# rs485.net
KiCad netlist of a schematic drawn in Altium Designer
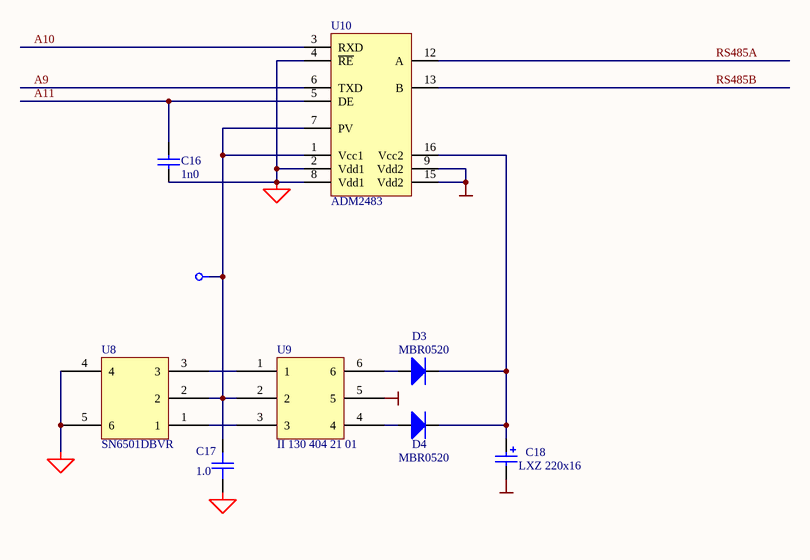
[diagram p0: rs485.SchDoc]

(export (version "E")
  (design (tool "Eeschema 10.0.6"))
  (components
    (comp (ref "C16")
      (value "1n0")
      (footprint "_1206")
      (description "Capacitor (Semiconductor SIM Model)")
      (fields (field (name "MANUFACTURER") "Generic Components") (field (name "PUBLISHER") "Altium Limited"))
      (libsource (lib "Miscellaneous Devices") (part "Cap Semi"))
    )
    (comp (ref "C17") (value "1.0") (footprint "_1206") (libsource (lib "C") (part "C_SM_1206")))
    (comp (ref "C18")
      (value "LXZ 220x16")
      (footprint "el3")
      (description "Polarized Capacitor (Radial)")
      (fields (field (name "MANUFACTURER") "Generic Components") (field (name "PUBLISHER") "Altium Limited"))
      (libsource (lib "PAL") (part "Cap Pol1"))
    )
    (comp (ref "D3")
      (value "MBR0520")
      (footprint "_1206d")
      (description "Default Diode")
      (fields (field (name "MANUFACTURER") "Generic Components") (field (name "PUBLISHER") "Altium Limited"))
      (libsource (lib "PAL") (part "Diode"))
    )
    (comp (ref "D4")
      (value "MBR0520")
      (footprint "_1206d")
      (description "Default Diode")
      (fields (field (name "MANUFACTURER") "Generic Components") (field (name "PUBLISHER") "Altium Limited"))
      (libsource (lib "PAL") (part "Diode"))
    )
    (comp (ref "U8") (value "SN6501DBVR") (footprint "SO-G5/P.95") (libsource (lib "CHIP") (part "PIN6")))
    (comp (ref "U9")
      (value "II 130 404 21 01")
      (footprint "II1304042101")
      (libsource (lib "") (part "PIN6_1"))
    )
    (comp (ref "U10") (value "ADM2483") (footprint "SO-G16/D10.4") (libsource (lib "PAL") (part "ADM2483")))
  )
  (nets
    (net (code "1") (name "+5v") (class "Default")
      (node (ref "C17") (pin "2") (pinfunction "2_2") (pintype "passive"))
      (node (ref "U10") (pin "1") (pinfunction "Vcc1_1") (pintype "passive"))
      (node (ref "U10") (pin "7") (pinfunction "PV_7") (pintype "passive"))
      (node (ref "U8") (pin "2") (pinfunction "2_2") (pintype "passive"))
      (node (ref "U9") (pin "2") (pinfunction "2_2") (pintype "passive"))
    )
    (net (code "2") (name "/A9") (class "Default")
      (node (ref "U10") (pin "6") (pinfunction "TXD_6") (pintype "passive"))
    )
    (net (code "3") (name "/A10") (class "Default")
      (node (ref "U10") (pin "3") (pinfunction "RXD_3") (pintype "passive"))
    )
    (net (code "4") (name "/A11") (class "Default")
      (node (ref "C16") (pin "2") (pinfunction "2_2") (pintype "passive"))
      (node (ref "U10") (pin "5") (pinfunction "DE_5") (pintype "passive"))
    )
    (net (code "5") (name "/RS485A") (class "Default")
      (node (ref "U10") (pin "12") (pinfunction "A_12") (pintype "passive"))
    )
    (net (code "6") (name "/RS485B") (class "Default")
      (node (ref "U10") (pin "13") (pinfunction "B_13") (pintype "passive"))
    )
    (net (code "7") (name "GND") (class "Default")
      (node (ref "C16") (pin "1") (pinfunction "1_1") (pintype "passive"))
      (node (ref "C17") (pin "1") (pinfunction "1_1") (pintype "passive"))
      (node (ref "U10") (pin "2") (pinfunction "Vdd1_2") (pintype "passive"))
      (node (ref "U10") (pin "4") (pinfunction "~{RE}_4") (pintype "passive"))
      (node (ref "U10") (pin "8") (pinfunction "Vdd1_8") (pintype "passive"))
      (node (ref "U8") (pin "4") (pinfunction "4_4") (pintype "passive"))
      (node (ref "U8") (pin "5") (pinfunction "6_5") (pintype "passive"))
    )
    (net (code "8") (name "GND_485") (class "Default")
      (node (ref "C18") (pin "2") (pinfunction "2_2") (pintype "passive"))
      (node (ref "U10") (pin "15") (pinfunction "Vdd2_15") (pintype "passive"))
      (node (ref "U10") (pin "9") (pinfunction "Vdd2_9") (pintype "passive"))
      (node (ref "U9") (pin "5") (pinfunction "5_5") (pintype "passive"))
    )
    (net (code "9") (name "Net-(D3-A)") (class "Default")
      (node (ref "D3") (pin "1") (pinfunction "A_1") (pintype "passive"))
      (node (ref "U9") (pin "6") (pinfunction "6_6") (pintype "passive"))
    )
    (net (code "10") (name "Net-(D3-K)") (class "Default")
      (node (ref "C18") (pin "1") (pinfunction "1_1") (pintype "passive"))
      (node (ref "D3") (pin "2") (pinfunction "K_2") (pintype "passive"))
      (node (ref "D4") (pin "2") (pinfunction "K_2") (pintype "passive"))
      (node (ref "U10") (pin "16") (pinfunction "Vcc2_16") (pintype "passive"))
    )
    (net (code "11") (name "Net-(D4-A)") (class "Default")
      (node (ref "D4") (pin "1") (pinfunction "A_1") (pintype "passive"))
      (node (ref "U9") (pin "4") (pinfunction "4_4") (pintype "passive"))
    )
    (net (code "12") (name "Net-(U8-Pad1)") (class "Default")
      (node (ref "U8") (pin "1") (pinfunction "1_1") (pintype "passive"))
      (node (ref "U9") (pin "3") (pinfunction "3_3") (pintype "passive"))
    )
    (net (code "13") (name "Net-(U8-Pad3)") (class "Default")
      (node (ref "U8") (pin "3") (pinfunction "3_3") (pintype "passive"))
      (node (ref "U9") (pin "1") (pinfunction "1_1") (pintype "passive"))
    )
    (net (code "14") (name "unconnected-(U8-5-Pad6)") (class "Default")
      (node (ref "U8") (pin "6") (pinfunction "5_6") (pintype "passive"))
    )
  )
)
